# MPU-Peripherals.net
KiCad netlist of a schematic drawn in Altium Designer
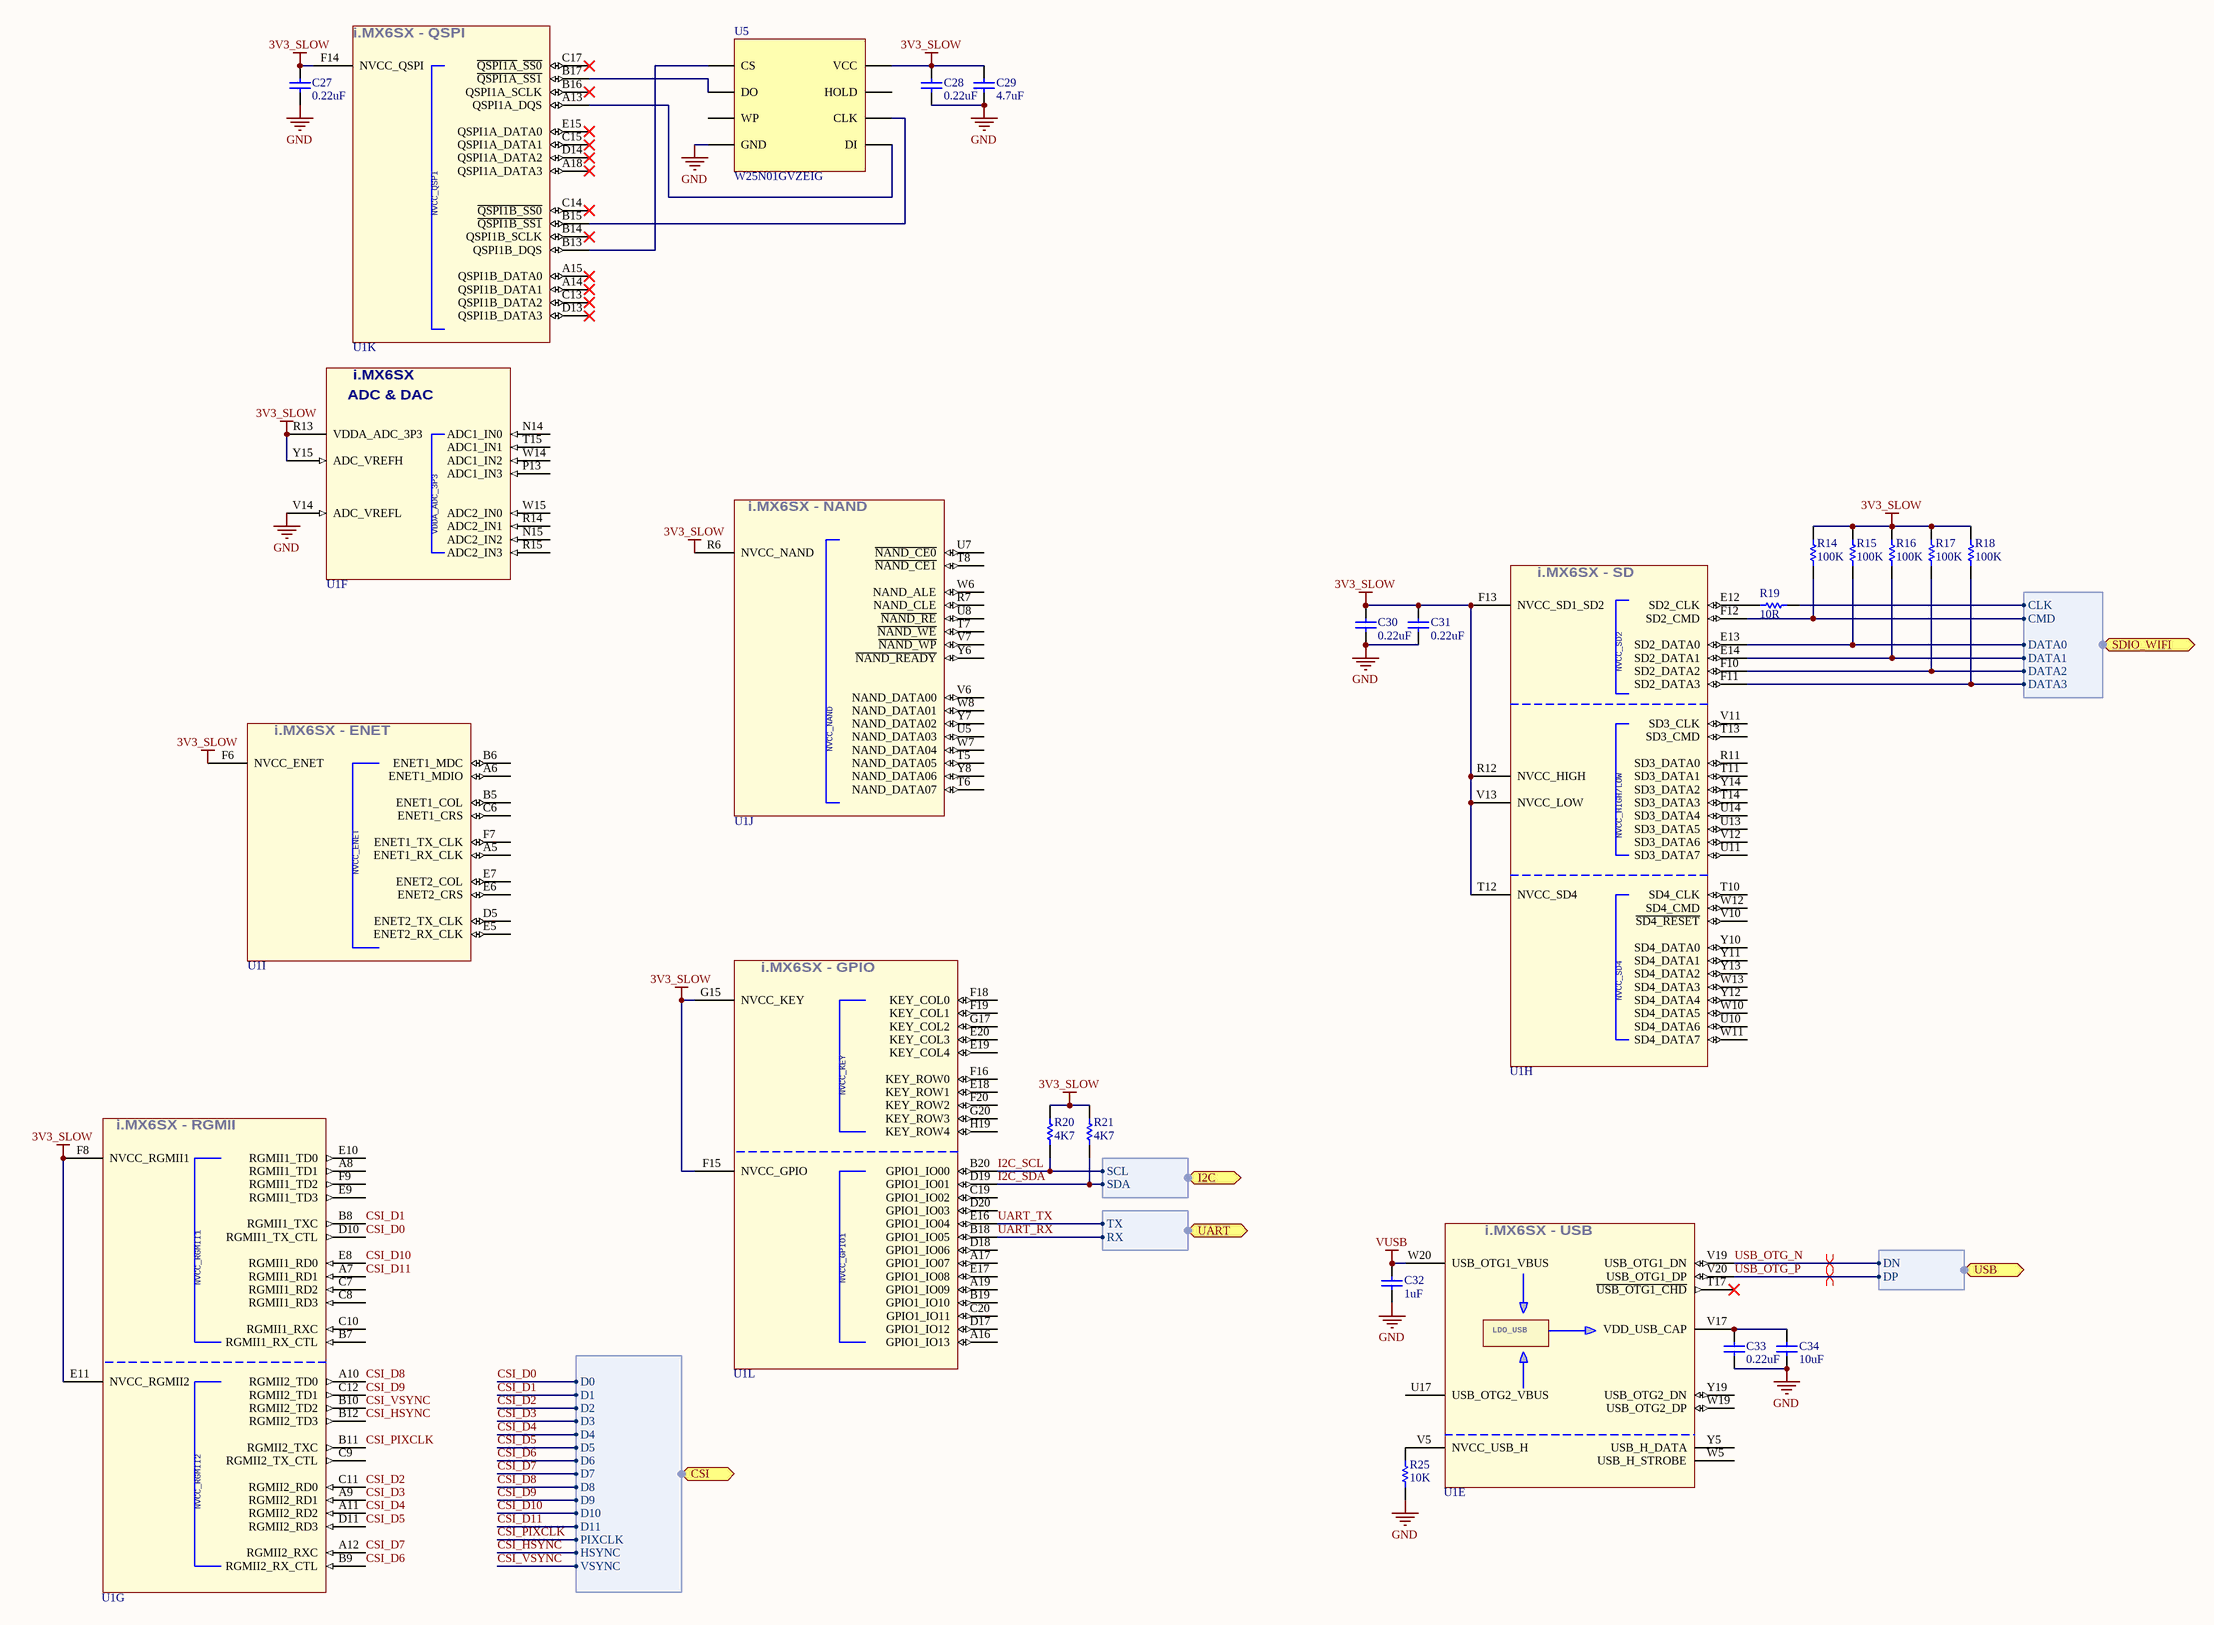
[diagram p0: MPU-Peripherals.SchDoc]

(export (version "E")
  (design (tool "Eeschema 10.0.6"))
  (components
    (comp (ref "C27")
      (value "0.22uF")
      (footprint "C0402[1005X55]")
      (description "0.22uF 6.3V 10% 0402 (1005 Metric)")
      (fields (field (name "PARTNUMBER") "JMK105BJ224KV-F") (field (name "MANUFACTURER") "Taiyo Yuden"))
      (libsource (lib "Capacitors") (part "CAP_0.22uF_6.3V_0402_10%"))
    )
    (comp (ref "C28")
      (value "0.22uF")
      (footprint "C0402[1005X55]")
      (description "0.22uF 6.3V 10% 0402 (1005 Metric)")
      (fields (field (name "PARTNUMBER") "JMK105BJ224KV-F") (field (name "MANUFACTURER") "Taiyo Yuden"))
      (libsource (lib "Capacitors") (part "CAP_0.22uF_6.3V_0402_10%"))
    )
    (comp (ref "C29")
      (value "4.7uF")
      (footprint "C0402[1005X55]")
      (description "4.7uF 6.3V 20% 0402 (1005 Metric)")
      (fields (field (name "PARTNUMBER") "GRM155R60J475ME47D") (field (name "MANUFACTURER") "Murata"))
      (libsource (lib "Capacitors") (part "CAP_4.7uF_6.3V_0402_20%"))
    )
    (comp (ref "C30")
      (value "0.22uF")
      (footprint "C0402[1005X55]")
      (description "0.22uF 6.3V 10% 0402 (1005 Metric)")
      (fields (field (name "PARTNUMBER") "JMK105BJ224KV-F") (field (name "MANUFACTURER") "Taiyo Yuden"))
      (libsource (lib "Capacitors") (part "CAP_0.22uF_6.3V_0402_10%"))
    )
    (comp (ref "C31")
      (value "0.22uF")
      (footprint "C0402[1005X55]")
      (description "0.22uF 6.3V 10% 0402 (1005 Metric)")
      (fields (field (name "PARTNUMBER") "JMK105BJ224KV-F") (field (name "MANUFACTURER") "Taiyo Yuden"))
      (libsource (lib "Capacitors") (part "CAP_0.22uF_6.3V_0402_10%"))
    )
    (comp (ref "C32")
      (value "1uF")
      (footprint "C0402[1005X55]")
      (description "1uF 16V 10% 0402 (1005 Metric)")
      (fields (field (name "PARTNUMBER") "GRM155R61C105KE01D") (field (name "MANUFACTURER") "Murata"))
      (libsource (lib "Capacitors") (part "CAP_1uF_16V_0402_10%"))
    )
    (comp (ref "C33")
      (value "0.22uF")
      (footprint "C0402[1005X55]")
      (description "0.22uF 6.3V 10% 0402 (1005 Metric)")
      (fields (field (name "PARTNUMBER") "JMK105BJ224KV-F") (field (name "MANUFACTURER") "Taiyo Yuden"))
      (libsource (lib "Capacitors") (part "CAP_0.22uF_6.3V_0402_10%"))
    )
    (comp (ref "C34")
      (value "10uF")
      (footprint "C0402[1005X55]")
      (description "10uF 6.3V 20% 0402 (1005 Metric)")
      (fields (field (name "PARTNUMBER") "GRM155R60J106ME44D") (field (name "MANUFACTURER") "Murata"))
      (libsource (lib "Capacitors") (part "CAP_10uF_6.3V_0402_20%"))
    )
    (comp (ref "R14")
      (value "100K")
      (footprint "R0402[1005]")
      (description "100K 0.063W 1% 0402 (1005 Metric)")
      (fields (field (name "MANUFACTURER") "KOA Speer") (field (name "PARTNUMBER") "RK73H1ETTP1003F"))
      (libsource (lib "Resistors") (part "RES_100K_0402_1%"))
    )
    (comp (ref "R15")
      (value "100K")
      (footprint "R0402[1005]")
      (description "100K 0.063W 1% 0402 (1005 Metric)")
      (fields (field (name "MANUFACTURER") "KOA Speer") (field (name "PARTNUMBER") "RK73H1ETTP1003F"))
      (libsource (lib "Resistors") (part "RES_100K_0402_1%"))
    )
    (comp (ref "R16")
      (value "100K")
      (footprint "R0402[1005]")
      (description "100K 0.063W 1% 0402 (1005 Metric)")
      (fields (field (name "MANUFACTURER") "KOA Speer") (field (name "PARTNUMBER") "RK73H1ETTP1003F"))
      (libsource (lib "Resistors") (part "RES_100K_0402_1%"))
    )
    (comp (ref "R17")
      (value "100K")
      (footprint "R0402[1005]")
      (description "100K 0.063W 1% 0402 (1005 Metric)")
      (fields (field (name "MANUFACTURER") "KOA Speer") (field (name "PARTNUMBER") "RK73H1ETTP1003F"))
      (libsource (lib "Resistors") (part "RES_100K_0402_1%"))
    )
    (comp (ref "R18")
      (value "100K")
      (footprint "R0402[1005]")
      (description "100K 0.063W 1% 0402 (1005 Metric)")
      (fields (field (name "MANUFACTURER") "KOA Speer") (field (name "PARTNUMBER") "RK73H1ETTP1003F"))
      (libsource (lib "Resistors") (part "RES_100K_0402_1%"))
    )
    (comp (ref "R19")
      (value "10R")
      (footprint "R0402[1005]")
      (description "10R 0.063W 1% 0402 (1005 Metric)")
      (fields (field (name "MANUFACTURER") "KOA Speer") (field (name "PARTNUMBER") "RK73H1ETTP10R0F"))
      (libsource (lib "Resistors") (part "RES_10R_0402_1%"))
    )
    (comp (ref "R20")
      (value "4K7")
      (footprint "R0402[1005]")
      (description "4K7 0.063W 1% 0402 (1005 Metric)")
      (fields (field (name "MANUFACTURER") "KOA Speer") (field (name "PARTNUMBER") "RK73H1ETTP4701F"))
      (libsource (lib "Resistors") (part "RES_4K7_0402_1%"))
    )
    (comp (ref "R21")
      (value "4K7")
      (footprint "R0402[1005]")
      (description "4K7 0.063W 1% 0402 (1005 Metric)")
      (fields (field (name "MANUFACTURER") "KOA Speer") (field (name "PARTNUMBER") "RK73H1ETTP4701F"))
      (libsource (lib "Resistors") (part "RES_4K7_0402_1%"))
    )
    (comp (ref "R25")
      (value "10K")
      (footprint "R0402[1005]")
      (description "10K 0.063W 1% 0402 (1005 Metric)")
      (fields (field (name "MANUFACTURER") "KOA Speer") (field (name "PARTNUMBER") "RK73H1ETTP1002F"))
      (libsource (lib "Resistors") (part "RES_10K_0402_1%"))
    )
    (comp (ref "U1")
      (value "MCIMX6X3EVO10AB")
      (footprint "BGA-400")
      (description "IC MPU I.MX6SX 1GHZ 400MAPBGA")
      (fields (field (name "MANUFACTURER") "NXP"))
      (libsource (lib "ICs") (part "MCIMX6X3EVO10AB"))
    )
    (comp (ref "U5")
      (value "W25N01GVZEIG")
      (footprint "WSON-8 (6X8MM)")
      (fields (field (name "MANUFACTURER") "Winbond Electronics"))
      (libsource (lib "ICs") (part "W25N01GVZEIG"))
    )
  )
  (nets
    (net (code "6") (name "/CLK") (class "Default")
      (node (ref "R19") (pin "2") (pinfunction "2_2") (pintype "passive"))
    )
    (net (code "7") (name "/CMD") (class "Default")
      (node (ref "R14") (pin "1") (pinfunction "1_1") (pintype "passive"))
      (node (ref "U1") (pin "F12") (pinfunction "SD2_CMD_F12") (pintype "bidirectional"))
    )
    (net (code "8") (name "/CSI_D0") (class "Default")
      (node (ref "U1") (pin "D10") (pinfunction "RGMII1_TX_CTL_D10") (pintype "output"))
    )
    (net (code "9") (name "/CSI_D1") (class "Default")
      (node (ref "U1") (pin "B8") (pinfunction "RGMII1_TXC_B8") (pintype "output"))
    )
    (net (code "10") (name "/CSI_D2") (class "Default")
      (node (ref "U1") (pin "C11") (pinfunction "RGMII2_RD0_C11") (pintype "input"))
    )
    (net (code "11") (name "/CSI_D3") (class "Default")
      (node (ref "U1") (pin "A9") (pinfunction "RGMII2_RD1_A9") (pintype "input"))
    )
    (net (code "12") (name "/CSI_D4") (class "Default")
      (node (ref "U1") (pin "A11") (pinfunction "RGMII2_RD2_A11") (pintype "input"))
    )
    (net (code "13") (name "/CSI_D5") (class "Default")
      (node (ref "U1") (pin "D11") (pinfunction "RGMII2_RD3_D11") (pintype "input"))
    )
    (net (code "14") (name "/CSI_D6") (class "Default")
      (node (ref "U1") (pin "B9") (pinfunction "RGMII2_RX_CTL_B9") (pintype "input"))
    )
    (net (code "15") (name "/CSI_D7") (class "Default")
      (node (ref "U1") (pin "A12") (pinfunction "RGMII2_RXC_A12") (pintype "input"))
    )
    (net (code "16") (name "/CSI_D8") (class "Default")
      (node (ref "U1") (pin "A10") (pinfunction "RGMII2_TD0_A10") (pintype "output"))
    )
    (net (code "17") (name "/CSI_D9") (class "Default")
      (node (ref "U1") (pin "C12") (pinfunction "RGMII2_TD1_C12") (pintype "output"))
    )
    (net (code "18") (name "/CSI_D10") (class "Default")
      (node (ref "U1") (pin "E8") (pinfunction "RGMII1_RD0_E8") (pintype "input"))
    )
    (net (code "19") (name "/CSI_D11") (class "Default")
      (node (ref "U1") (pin "A7") (pinfunction "RGMII1_RD1_A7") (pintype "input"))
    )
    (net (code "20") (name "/CSI_HSYNC") (class "Default")
      (node (ref "U1") (pin "B12") (pinfunction "RGMII2_TD3_B12") (pintype "output"))
    )
    (net (code "21") (name "/CSI_PIXCLK") (class "Default")
      (node (ref "U1") (pin "B11") (pinfunction "RGMII2_TXC_B11") (pintype "output"))
    )
    (net (code "22") (name "/CSI_VSYNC") (class "Default")
      (node (ref "U1") (pin "B10") (pinfunction "RGMII2_TD2_B10") (pintype "output"))
    )
    (net (code "23") (name "/DATA0") (class "Default")
      (node (ref "R15") (pin "1") (pinfunction "1_1") (pintype "passive"))
      (node (ref "U1") (pin "E13") (pinfunction "SD2_DATA0_E13") (pintype "bidirectional"))
    )
    (net (code "24") (name "/DATA1") (class "Default")
      (node (ref "R16") (pin "1") (pinfunction "1_1") (pintype "passive"))
      (node (ref "U1") (pin "E14") (pinfunction "SD2_DATA1_E14") (pintype "bidirectional"))
    )
    (net (code "25") (name "/DATA2") (class "Default")
      (node (ref "R17") (pin "1") (pinfunction "1_1") (pintype "passive"))
      (node (ref "U1") (pin "F10") (pinfunction "SD2_DATA2_F10") (pintype "bidirectional"))
    )
    (net (code "26") (name "/DATA3") (class "Default")
      (node (ref "R18") (pin "1") (pinfunction "1_1") (pintype "passive"))
      (node (ref "U1") (pin "F11") (pinfunction "SD2_DATA3_F11") (pintype "bidirectional"))
    )
    (net (code "27") (name "/I2C_SCL") (class "Default")
      (node (ref "R20") (pin "1") (pinfunction "1_1") (pintype "passive"))
      (node (ref "U1") (pin "B20") (pinfunction "GPIO1_IO00_B20") (pintype "bidirectional"))
    )
    (net (code "28") (name "/I2C_SDA") (class "Default")
      (node (ref "R21") (pin "1") (pinfunction "1_1") (pintype "passive"))
      (node (ref "U1") (pin "D19") (pinfunction "GPIO1_IO01_D19") (pintype "bidirectional"))
    )
    (net (code "29") (name "/UART_RX") (class "Default")
      (node (ref "U1") (pin "B18") (pinfunction "GPIO1_IO05_B18") (pintype "bidirectional"))
    )
    (net (code "30") (name "/UART_TX") (class "Default")
      (node (ref "U1") (pin "E16") (pinfunction "GPIO1_IO04_E16") (pintype "bidirectional"))
    )
    (net (code "31") (name "/USB_OTG_N") (class "Default")
      (node (ref "U1") (pin "V19") (pinfunction "USB_OTG1_DN_V19") (pintype "bidirectional"))
    )
    (net (code "32") (name "/USB_OTG_P") (class "Default")
      (node (ref "U1") (pin "V20") (pinfunction "USB_OTG1_DP_V20") (pintype "bidirectional"))
    )
    (net (code "38") (name "3V3_SLOW") (class "Default")
      (node (ref "C27") (pin "2") (pinfunction "2_2") (pintype "passive"))
      (node (ref "C28") (pin "2") (pinfunction "2_2") (pintype "passive"))
      (node (ref "C29") (pin "2") (pinfunction "2_2") (pintype "passive"))
      (node (ref "C30") (pin "2") (pinfunction "2_2") (pintype "passive"))
      (node (ref "C31") (pin "2") (pinfunction "2_2") (pintype "passive"))
      (node (ref "R14") (pin "2") (pinfunction "2_2") (pintype "passive"))
      (node (ref "R15") (pin "2") (pinfunction "2_2") (pintype "passive"))
      (node (ref "R16") (pin "2") (pinfunction "2_2") (pintype "passive"))
      (node (ref "R17") (pin "2") (pinfunction "2_2") (pintype "passive"))
      (node (ref "R18") (pin "2") (pinfunction "2_2") (pintype "passive"))
      (node (ref "R20") (pin "2") (pinfunction "2_2") (pintype "passive"))
      (node (ref "R21") (pin "2") (pinfunction "2_2") (pintype "passive"))
      (node (ref "U1") (pin "E11") (pinfunction "NVCC_RGMII2_E11") (pintype "power_in"))
      (node (ref "U1") (pin "F13") (pinfunction "NVCC_SD1_SD2_F13") (pintype "power_in"))
      (node (ref "U1") (pin "F14") (pinfunction "NVCC_QSPI_F14") (pintype "power_in"))
      (node (ref "U1") (pin "F15") (pinfunction "NVCC_GPIO_F15") (pintype "power_in"))
      (node (ref "U1") (pin "F6") (pinfunction "NVCC_ENET_F6") (pintype "power_in"))
      (node (ref "U1") (pin "F8") (pinfunction "NVCC_RGMII1_F8") (pintype "power_in"))
      (node (ref "U1") (pin "G15") (pinfunction "NVCC_KEY_G15") (pintype "power_in"))
      (node (ref "U1") (pin "R12") (pinfunction "NVCC_HIGH_R12") (pintype "power_in"))
      (node (ref "U1") (pin "R13") (pinfunction "VDDA_ADC_3P3_R13") (pintype "power_in"))
      (node (ref "U1") (pin "R6") (pinfunction "NVCC_NAND_R6") (pintype "power_in"))
      (node (ref "U1") (pin "T12") (pinfunction "NVCC_SD4_T12") (pintype "power_in"))
      (node (ref "U1") (pin "V13") (pinfunction "NVCC_LOW_V13") (pintype "power_in"))
      (node (ref "U1") (pin "Y15") (pinfunction "ADC_VREFH_Y15") (pintype "input"))
      (node (ref "U5") (pin "8") (pinfunction "VCC_8") (pintype "passive"))
    )
    (net (code "39") (name "GND") (class "Default")
      (node (ref "C27") (pin "1") (pinfunction "1_1") (pintype "passive"))
      (node (ref "C28") (pin "1") (pinfunction "1_1") (pintype "passive"))
      (node (ref "C29") (pin "1") (pinfunction "1_1") (pintype "passive"))
      (node (ref "C30") (pin "1") (pinfunction "1_1") (pintype "passive"))
      (node (ref "C31") (pin "1") (pinfunction "1_1") (pintype "passive"))
      (node (ref "C32") (pin "1") (pinfunction "1_1") (pintype "passive"))
      (node (ref "C33") (pin "1") (pinfunction "1_1") (pintype "passive"))
      (node (ref "C34") (pin "1") (pinfunction "1_1") (pintype "passive"))
      (node (ref "R25") (pin "1") (pinfunction "1_1") (pintype "passive"))
      (node (ref "U1") (pin "V14") (pinfunction "ADC_VREFL_V14") (pintype "input"))
      (node (ref "U5") (pin "4") (pinfunction "GND_4") (pintype "passive"))
    )
    (net (code "40") (name "Net-(U1E-NVCC_USB_H)") (class "Default")
      (node (ref "R25") (pin "2") (pinfunction "2_2") (pintype "passive"))
      (node (ref "U1") (pin "V5") (pinfunction "NVCC_USB_H_V5") (pintype "power_in"))
    )
    (net (code "41") (name "Net-(U1E-VDD_USB_CAP)") (class "Default")
      (node (ref "C33") (pin "2") (pinfunction "2_2") (pintype "passive"))
      (node (ref "C34") (pin "2") (pinfunction "2_2") (pintype "passive"))
      (node (ref "U1") (pin "V17") (pinfunction "VDD_USB_CAP_V17") (pintype "power_in"))
    )
    (net (code "42") (name "Net-(U1H-SD2_CLK)") (class "Default")
      (node (ref "R19") (pin "1") (pinfunction "1_1") (pintype "passive"))
      (node (ref "U1") (pin "E12") (pinfunction "SD2_CLK_E12") (pintype "bidirectional"))
    )
    (net (code "43") (name "Net-(U1K-QSPI1A_DQS)") (class "Default")
      (node (ref "U1") (pin "A13") (pinfunction "QSPI1A_DQS_A13") (pintype "bidirectional"))
      (node (ref "U5") (pin "5") (pinfunction "DI_5") (pintype "power_in"))
    )
    (net (code "44") (name "Net-(U1K-QSPI1B_DQS)") (class "Default")
      (node (ref "U1") (pin "B13") (pinfunction "QSPI1B_DQS_B13") (pintype "bidirectional"))
      (node (ref "U5") (pin "1") (pinfunction "CS_1") (pintype "passive"))
    )
    (net (code "45") (name "Net-(U1K-~{QSPI1A_SS1})") (class "Default")
      (node (ref "U1") (pin "B17") (pinfunction "~{QSPI1A_SS1}_B17") (pintype "bidirectional"))
      (node (ref "U5") (pin "2") (pinfunction "DO_2") (pintype "passive"))
    )
    (net (code "46") (name "Net-(U1K-~{QSPI1B_SS1})") (class "Default")
      (node (ref "U1") (pin "B15") (pinfunction "~{QSPI1B_SS1}_B15") (pintype "bidirectional"))
      (node (ref "U5") (pin "6") (pinfunction "CLK_6") (pintype "passive"))
    )
    (net (code "47") (name "VUSB") (class "Default")
      (node (ref "C32") (pin "2") (pinfunction "2_2") (pintype "passive"))
      (node (ref "U1") (pin "W20") (pinfunction "USB_OTG1_VBUS_W20") (pintype "power_in"))
    )
    (net (code "48") (name "unconnected-(U1E-USB_H_DATA-PadY5)") (class "Default")
      (node (ref "U1") (pin "Y5") (pinfunction "USB_H_DATA_Y5") (pintype "passive"))
    )
    (net (code "49") (name "unconnected-(U1E-USB_H_STROBE-PadW5)") (class "Default")
      (node (ref "U1") (pin "W5") (pinfunction "USB_H_STROBE_W5") (pintype "passive"))
    )
    (net (code "50") (name "unconnected-(U1E-USB_OTG2_DN-PadY19)") (class "Default")
      (node (ref "U1") (pin "Y19") (pinfunction "USB_OTG2_DN_Y19") (pintype "bidirectional"))
    )
    (net (code "51") (name "unconnected-(U1E-USB_OTG2_DP-PadW19)") (class "Default")
      (node (ref "U1") (pin "W19") (pinfunction "USB_OTG2_DP_W19") (pintype "bidirectional"))
    )
    (net (code "52") (name "unconnected-(U1E-USB_OTG2_VBUS-PadU17)") (class "Default")
      (node (ref "U1") (pin "U17") (pinfunction "USB_OTG2_VBUS_U17") (pintype "power_in"))
    )
    (net (code "53") (name "unconnected-(U1E-~{USB_OTG1_CHD}-PadT17)") (class "Default")
      (node (ref "U1") (pin "T17") (pinfunction "~{USB_OTG1_CHD}_T17") (pintype "output+no_connect"))
    )
    (net (code "54") (name "unconnected-(U1F-ADC1_IN0-PadN14)") (class "Default")
      (node (ref "U1") (pin "N14") (pinfunction "ADC1_IN0_N14") (pintype "input"))
    )
    (net (code "55") (name "unconnected-(U1F-ADC1_IN1-PadT15)") (class "Default")
      (node (ref "U1") (pin "T15") (pinfunction "ADC1_IN1_T15") (pintype "input"))
    )
    (net (code "56") (name "unconnected-(U1F-ADC1_IN2-PadW14)") (class "Default")
      (node (ref "U1") (pin "W14") (pinfunction "ADC1_IN2_W14") (pintype "input"))
    )
    (net (code "57") (name "unconnected-(U1F-ADC1_IN3-PadP13)") (class "Default")
      (node (ref "U1") (pin "P13") (pinfunction "ADC1_IN3_P13") (pintype "input"))
    )
    (net (code "58") (name "unconnected-(U1F-ADC2_IN0-PadW15)") (class "Default")
      (node (ref "U1") (pin "W15") (pinfunction "ADC2_IN0_W15") (pintype "input"))
    )
    (net (code "59") (name "unconnected-(U1F-ADC2_IN1-PadR14)") (class "Default")
      (node (ref "U1") (pin "R14") (pinfunction "ADC2_IN1_R14") (pintype "input"))
    )
    (net (code "60") (name "unconnected-(U1F-ADC2_IN2-PadN15)") (class "Default")
      (node (ref "U1") (pin "N15") (pinfunction "ADC2_IN2_N15") (pintype "input"))
    )
    (net (code "61") (name "unconnected-(U1F-ADC2_IN3-PadR15)") (class "Default")
      (node (ref "U1") (pin "R15") (pinfunction "ADC2_IN3_R15") (pintype "input"))
    )
    (net (code "62") (name "unconnected-(U1G-RGMII1_RD2-PadC7)") (class "Default")
      (node (ref "U1") (pin "C7") (pinfunction "RGMII1_RD2_C7") (pintype "input"))
    )
    (net (code "63") (name "unconnected-(U1G-RGMII1_RD3-PadC8)") (class "Default")
      (node (ref "U1") (pin "C8") (pinfunction "RGMII1_RD3_C8") (pintype "input"))
    )
    (net (code "64") (name "unconnected-(U1G-RGMII1_RXC-PadC10)") (class "Default")
      (node (ref "U1") (pin "C10") (pinfunction "RGMII1_RXC_C10") (pintype "input"))
    )
    (net (code "65") (name "unconnected-(U1G-RGMII1_RX_CTL-PadB7)") (class "Default")
      (node (ref "U1") (pin "B7") (pinfunction "RGMII1_RX_CTL_B7") (pintype "input"))
    )
    (net (code "66") (name "unconnected-(U1G-RGMII1_TD0-PadE10)") (class "Default")
      (node (ref "U1") (pin "E10") (pinfunction "RGMII1_TD0_E10") (pintype "output"))
    )
    (net (code "67") (name "unconnected-(U1G-RGMII1_TD1-PadA8)") (class "Default")
      (node (ref "U1") (pin "A8") (pinfunction "RGMII1_TD1_A8") (pintype "output"))
    )
    (net (code "68") (name "unconnected-(U1G-RGMII1_TD2-PadF9)") (class "Default")
      (node (ref "U1") (pin "F9") (pinfunction "RGMII1_TD2_F9") (pintype "output"))
    )
    (net (code "69") (name "unconnected-(U1G-RGMII1_TD3-PadE9)") (class "Default")
      (node (ref "U1") (pin "E9") (pinfunction "RGMII1_TD3_E9") (pintype "output"))
    )
    (net (code "70") (name "unconnected-(U1G-RGMII2_TX_CTL-PadC9)") (class "Default")
      (node (ref "U1") (pin "C9") (pinfunction "RGMII2_TX_CTL_C9") (pintype "output"))
    )
    (net (code "71") (name "unconnected-(U1H-SD3_CLK-PadV11)") (class "Default")
      (node (ref "U1") (pin "V11") (pinfunction "SD3_CLK_V11") (pintype "bidirectional"))
    )
    (net (code "72") (name "unconnected-(U1H-SD3_CMD-PadT13)") (class "Default")
      (node (ref "U1") (pin "T13") (pinfunction "SD3_CMD_T13") (pintype "bidirectional"))
    )
    (net (code "73") (name "unconnected-(U1H-SD3_DATA0-PadR11)") (class "Default")
      (node (ref "U1") (pin "R11") (pinfunction "SD3_DATA0_R11") (pintype "bidirectional"))
    )
    (net (code "74") (name "unconnected-(U1H-SD3_DATA1-PadT11)") (class "Default")
      (node (ref "U1") (pin "T11") (pinfunction "SD3_DATA1_T11") (pintype "bidirectional"))
    )
    (net (code "75") (name "unconnected-(U1H-SD3_DATA2-PadY14)") (class "Default")
      (node (ref "U1") (pin "Y14") (pinfunction "SD3_DATA2_Y14") (pintype "bidirectional"))
    )
    (net (code "76") (name "unconnected-(U1H-SD3_DATA3-PadT14)") (class "Default")
      (node (ref "U1") (pin "T14") (pinfunction "SD3_DATA3_T14") (pintype "bidirectional"))
    )
    (net (code "77") (name "unconnected-(U1H-SD3_DATA4-PadU14)") (class "Default")
      (node (ref "U1") (pin "U14") (pinfunction "SD3_DATA4_U14") (pintype "bidirectional"))
    )
    (net (code "78") (name "unconnected-(U1H-SD3_DATA5-PadU13)") (class "Default")
      (node (ref "U1") (pin "U13") (pinfunction "SD3_DATA5_U13") (pintype "bidirectional"))
    )
    (net (code "79") (name "unconnected-(U1H-SD3_DATA6-PadV12)") (class "Default")
      (node (ref "U1") (pin "V12") (pinfunction "SD3_DATA6_V12") (pintype "bidirectional"))
    )
    (net (code "80") (name "unconnected-(U1H-SD3_DATA7-PadU11)") (class "Default")
      (node (ref "U1") (pin "U11") (pinfunction "SD3_DATA7_U11") (pintype "bidirectional"))
    )
    (net (code "81") (name "unconnected-(U1H-SD4_CLK-PadT10)") (class "Default")
      (node (ref "U1") (pin "T10") (pinfunction "SD4_CLK_T10") (pintype "bidirectional"))
    )
    (net (code "82") (name "unconnected-(U1H-SD4_CMD-PadW12)") (class "Default")
      (node (ref "U1") (pin "W12") (pinfunction "SD4_CMD_W12") (pintype "bidirectional"))
    )
    (net (code "83") (name "unconnected-(U1H-SD4_DATA0-PadY10)") (class "Default")
      (node (ref "U1") (pin "Y10") (pinfunction "SD4_DATA0_Y10") (pintype "bidirectional"))
    )
    (net (code "84") (name "unconnected-(U1H-SD4_DATA1-PadY11)") (class "Default")
      (node (ref "U1") (pin "Y11") (pinfunction "SD4_DATA1_Y11") (pintype "bidirectional"))
    )
    (net (code "85") (name "unconnected-(U1H-SD4_DATA2-PadY13)") (class "Default")
      (node (ref "U1") (pin "Y13") (pinfunction "SD4_DATA2_Y13") (pintype "bidirectional"))
    )
    (net (code "86") (name "unconnected-(U1H-SD4_DATA3-PadW13)") (class "Default")
      (node (ref "U1") (pin "W13") (pinfunction "SD4_DATA3_W13") (pintype "bidirectional"))
    )
    (net (code "87") (name "unconnected-(U1H-SD4_DATA4-PadY12)") (class "Default")
      (node (ref "U1") (pin "Y12") (pinfunction "SD4_DATA4_Y12") (pintype "bidirectional"))
    )
    (net (code "88") (name "unconnected-(U1H-SD4_DATA5-PadW10)") (class "Default")
      (node (ref "U1") (pin "W10") (pinfunction "SD4_DATA5_W10") (pintype "bidirectional"))
    )
    (net (code "89") (name "unconnected-(U1H-SD4_DATA6-PadU10)") (class "Default")
      (node (ref "U1") (pin "U10") (pinfunction "SD4_DATA6_U10") (pintype "bidirectional"))
    )
    (net (code "90") (name "unconnected-(U1H-SD4_DATA7-PadW11)") (class "Default")
      (node (ref "U1") (pin "W11") (pinfunction "SD4_DATA7_W11") (pintype "bidirectional"))
    )
    (net (code "91") (name "unconnected-(U1H-~{SD4_RESET}-PadV10)") (class "Default")
      (node (ref "U1") (pin "V10") (pinfunction "~{SD4_RESET}_V10") (pintype "bidirectional"))
    )
    (net (code "92") (name "unconnected-(U1I-ENET1_COL-PadB5)") (class "Default")
      (node (ref "U1") (pin "B5") (pinfunction "ENET1_COL_B5") (pintype "bidirectional"))
    )
    (net (code "93") (name "unconnected-(U1I-ENET1_CRS-PadC6)") (class "Default")
      (node (ref "U1") (pin "C6") (pinfunction "ENET1_CRS_C6") (pintype "bidirectional"))
    )
    (net (code "94") (name "unconnected-(U1I-ENET1_MDC-PadB6)") (class "Default")
      (node (ref "U1") (pin "B6") (pinfunction "ENET1_MDC_B6") (pintype "bidirectional"))
    )
    (net (code "95") (name "unconnected-(U1I-ENET1_MDIO-PadA6)") (class "Default")
      (node (ref "U1") (pin "A6") (pinfunction "ENET1_MDIO_A6") (pintype "bidirectional"))
    )
    (net (code "96") (name "unconnected-(U1I-ENET1_RX_CLK-PadA5)") (class "Default")
      (node (ref "U1") (pin "A5") (pinfunction "ENET1_RX_CLK_A5") (pintype "bidirectional"))
    )
    (net (code "97") (name "unconnected-(U1I-ENET1_TX_CLK-PadF7)") (class "Default")
      (node (ref "U1") (pin "F7") (pinfunction "ENET1_TX_CLK_F7") (pintype "bidirectional"))
    )
    (net (code "98") (name "unconnected-(U1I-ENET2_COL-PadE7)") (class "Default")
      (node (ref "U1") (pin "E7") (pinfunction "ENET2_COL_E7") (pintype "bidirectional"))
    )
    (net (code "99") (name "unconnected-(U1I-ENET2_CRS-PadE6)") (class "Default")
      (node (ref "U1") (pin "E6") (pinfunction "ENET2_CRS_E6") (pintype "bidirectional"))
    )
    (net (code "100") (name "unconnected-(U1I-ENET2_RX_CLK-PadE5)") (class "Default")
      (node (ref "U1") (pin "E5") (pinfunction "ENET2_RX_CLK_E5") (pintype "bidirectional"))
    )
    (net (code "101") (name "unconnected-(U1I-ENET2_TX_CLK-PadD5)") (class "Default")
      (node (ref "U1") (pin "D5") (pinfunction "ENET2_TX_CLK_D5") (pintype "bidirectional"))
    )
    (net (code "102") (name "unconnected-(U1J-NAND_ALE-PadW6)") (class "Default")
      (node (ref "U1") (pin "W6") (pinfunction "NAND_ALE_W6") (pintype "bidirectional"))
    )
    (net (code "103") (name "unconnected-(U1J-NAND_CLE-PadR7)") (class "Default")
      (node (ref "U1") (pin "R7") (pinfunction "NAND_CLE_R7") (pintype "bidirectional"))
    )
    (net (code "104") (name "unconnected-(U1J-NAND_DATA00-PadV6)") (class "Default")
      (node (ref "U1") (pin "V6") (pinfunction "NAND_DATA00_V6") (pintype "bidirectional"))
    )
    (net (code "105") (name "unconnected-(U1J-NAND_DATA01-PadW8)") (class "Default")
      (node (ref "U1") (pin "W8") (pinfunction "NAND_DATA01_W8") (pintype "bidirectional"))
    )
    (net (code "106") (name "unconnected-(U1J-NAND_DATA02-PadY7)") (class "Default")
      (node (ref "U1") (pin "Y7") (pinfunction "NAND_DATA02_Y7") (pintype "bidirectional"))
    )
    (net (code "107") (name "unconnected-(U1J-NAND_DATA03-PadU5)") (class "Default")
      (node (ref "U1") (pin "U5") (pinfunction "NAND_DATA03_U5") (pintype "bidirectional"))
    )
    (net (code "108") (name "unconnected-(U1J-NAND_DATA04-PadW7)") (class "Default")
      (node (ref "U1") (pin "W7") (pinfunction "NAND_DATA04_W7") (pintype "bidirectional"))
    )
    (net (code "109") (name "unconnected-(U1J-NAND_DATA05-PadT5)") (class "Default")
      (node (ref "U1") (pin "T5") (pinfunction "NAND_DATA05_T5") (pintype "bidirectional"))
    )
    (net (code "110") (name "unconnected-(U1J-NAND_DATA06-PadY8)") (class "Default")
      (node (ref "U1") (pin "Y8") (pinfunction "NAND_DATA06_Y8") (pintype "bidirectional"))
    )
    (net (code "111") (name "unconnected-(U1J-NAND_DATA07-PadT6)") (class "Default")
      (node (ref "U1") (pin "T6") (pinfunction "NAND_DATA07_T6") (pintype "bidirectional"))
    )
    (net (code "112") (name "unconnected-(U1J-~{NAND_CE0}-PadU7)") (class "Default")
      (node (ref "U1") (pin "U7") (pinfunction "~{NAND_CE0}_U7") (pintype "bidirectional"))
    )
    (net (code "113") (name "unconnected-(U1J-~{NAND_CE1}-PadT8)") (class "Default")
      (node (ref "U1") (pin "T8") (pinfunction "~{NAND_CE1}_T8") (pintype "bidirectional"))
    )
    (net (code "114") (name "unconnected-(U1J-~{NAND_READY}-PadY6)") (class "Default")
      (node (ref "U1") (pin "Y6") (pinfunction "~{NAND_READY}_Y6") (pintype "bidirectional"))
    )
    (net (code "115") (name "unconnected-(U1J-~{NAND_RE}-PadU8)") (class "Default")
      (node (ref "U1") (pin "U8") (pinfunction "~{NAND_RE}_U8") (pintype "bidirectional"))
    )
    (net (code "116") (name "unconnected-(U1J-~{NAND_WE}-PadT7)") (class "Default")
      (node (ref "U1") (pin "T7") (pinfunction "~{NAND_WE}_T7") (pintype "bidirectional"))
    )
    (net (code "117") (name "unconnected-(U1J-~{NAND_WP}-PadV7)") (class "Default")
      (node (ref "U1") (pin "V7") (pinfunction "~{NAND_WP}_V7") (pintype "bidirectional"))
    )
    (net (code "118") (name "unconnected-(U1K-QSPI1A_DATA0-PadE15)") (class "Default")
      (node (ref "U1") (pin "E15") (pinfunction "QSPI1A_DATA0_E15") (pintype "bidirectional+no_connect"))
    )
    (net (code "119") (name "unconnected-(U1K-QSPI1A_DATA1-PadC15)") (class "Default")
      (node (ref "U1") (pin "C15") (pinfunction "QSPI1A_DATA1_C15") (pintype "bidirectional+no_connect"))
    )
    (net (code "120") (name "unconnected-(U1K-QSPI1A_DATA2-PadD14)") (class "Default")
      (node (ref "U1") (pin "D14") (pinfunction "QSPI1A_DATA2_D14") (pintype "bidirectional+no_connect"))
    )
    (net (code "121") (name "unconnected-(U1K-QSPI1A_DATA3-PadA18)") (class "Default")
      (node (ref "U1") (pin "A18") (pinfunction "QSPI1A_DATA3_A18") (pintype "bidirectional+no_connect"))
    )
    (net (code "122") (name "unconnected-(U1K-QSPI1A_SCLK-PadB16)") (class "Default")
      (node (ref "U1") (pin "B16") (pinfunction "QSPI1A_SCLK_B16") (pintype "bidirectional+no_connect"))
    )
    (net (code "123") (name "unconnected-(U1K-QSPI1B_DATA0-PadA15)") (class "Default")
      (node (ref "U1") (pin "A15") (pinfunction "QSPI1B_DATA0_A15") (pintype "bidirectional+no_connect"))
    )
    (net (code "124") (name "unconnected-(U1K-QSPI1B_DATA1-PadA14)") (class "Default")
      (node (ref "U1") (pin "A14") (pinfunction "QSPI1B_DATA1_A14") (pintype "bidirectional+no_connect"))
    )
    (net (code "125") (name "unconnected-(U1K-QSPI1B_DATA2-PadC13)") (class "Default")
      (node (ref "U1") (pin "C13") (pinfunction "QSPI1B_DATA2_C13") (pintype "bidirectional+no_connect"))
    )
    (net (code "126") (name "unconnected-(U1K-QSPI1B_DATA3-PadD13)") (class "Default")
      (node (ref "U1") (pin "D13") (pinfunction "QSPI1B_DATA3_D13") (pintype "bidirectional+no_connect"))
    )
    (net (code "127") (name "unconnected-(U1K-QSPI1B_SCLK-PadB14)") (class "Default")
      (node (ref "U1") (pin "B14") (pinfunction "QSPI1B_SCLK_B14") (pintype "bidirectional+no_connect"))
    )
    (net (code "128") (name "unconnected-(U1K-~{QSPI1A}_~{SS0}-PadC17)") (class "Default")
      (node (ref "U1") (pin "C17") (pinfunction "~{QSPI1A}_~{SS0}_C17") (pintype "bidirectional+no_connect"))
    )
    (net (code "129") (name "unconnected-(U1K-~{QSPI1B_SS0}-PadC14)") (class "Default")
      (node (ref "U1") (pin "C14") (pinfunction "~{QSPI1B_SS0}_C14") (pintype "bidirectional+no_connect"))
    )
    (net (code "130") (name "unconnected-(U1L-GPIO1_IO02-PadC19)") (class "Default")
      (node (ref "U1") (pin "C19") (pinfunction "GPIO1_IO02_C19") (pintype "bidirectional"))
    )
    (net (code "131") (name "unconnected-(U1L-GPIO1_IO03-PadD20)") (class "Default")
      (node (ref "U1") (pin "D20") (pinfunction "GPIO1_IO03_D20") (pintype "bidirectional"))
    )
    (net (code "132") (name "unconnected-(U1L-GPIO1_IO06-PadD18)") (class "Default")
      (node (ref "U1") (pin "D18") (pinfunction "GPIO1_IO06_D18") (pintype "bidirectional"))
    )
    (net (code "133") (name "unconnected-(U1L-GPIO1_IO07-PadA17)") (class "Default")
      (node (ref "U1") (pin "A17") (pinfunction "GPIO1_IO07_A17") (pintype "bidirectional"))
    )
    (net (code "134") (name "unconnected-(U1L-GPIO1_IO08-PadE17)") (class "Default")
      (node (ref "U1") (pin "E17") (pinfunction "GPIO1_IO08_E17") (pintype "bidirectional"))
    )
    (net (code "135") (name "unconnected-(U1L-GPIO1_IO09-PadA19)") (class "Default")
      (node (ref "U1") (pin "A19") (pinfunction "GPIO1_IO09_A19") (pintype "bidirectional"))
    )
    (net (code "136") (name "unconnected-(U1L-GPIO1_IO10-PadB19)") (class "Default")
      (node (ref "U1") (pin "B19") (pinfunction "GPIO1_IO10_B19") (pintype "bidirectional"))
    )
    (net (code "137") (name "unconnected-(U1L-GPIO1_IO11-PadC20)") (class "Default")
      (node (ref "U1") (pin "C20") (pinfunction "GPIO1_IO11_C20") (pintype "bidirectional"))
    )
    (net (code "138") (name "unconnected-(U1L-GPIO1_IO12-PadD17)") (class "Default")
      (node (ref "U1") (pin "D17") (pinfunction "GPIO1_IO12_D17") (pintype "bidirectional"))
    )
    (net (code "139") (name "unconnected-(U1L-GPIO1_IO13-PadA16)") (class "Default")
      (node (ref "U1") (pin "A16") (pinfunction "GPIO1_IO13_A16") (pintype "bidirectional"))
    )
    (net (code "140") (name "unconnected-(U1L-KEY_COL0-PadF18)") (class "Default")
      (node (ref "U1") (pin "F18") (pinfunction "KEY_COL0_F18") (pintype "bidirectional"))
    )
    (net (code "141") (name "unconnected-(U1L-KEY_COL1-PadF19)") (class "Default")
      (node (ref "U1") (pin "F19") (pinfunction "KEY_COL1_F19") (pintype "bidirectional"))
    )
    (net (code "142") (name "unconnected-(U1L-KEY_COL2-PadG17)") (class "Default")
      (node (ref "U1") (pin "G17") (pinfunction "KEY_COL2_G17") (pintype "bidirectional"))
    )
    (net (code "143") (name "unconnected-(U1L-KEY_COL3-PadE20)") (class "Default")
      (node (ref "U1") (pin "E20") (pinfunction "KEY_COL3_E20") (pintype "bidirectional"))
    )
    (net (code "144") (name "unconnected-(U1L-KEY_COL4-PadE19)") (class "Default")
      (node (ref "U1") (pin "E19") (pinfunction "KEY_COL4_E19") (pintype "bidirectional"))
    )
    (net (code "145") (name "unconnected-(U1L-KEY_ROW0-PadF16)") (class "Default")
      (node (ref "U1") (pin "F16") (pinfunction "KEY_ROW0_F16") (pintype "bidirectional"))
    )
    (net (code "146") (name "unconnected-(U1L-KEY_ROW1-PadE18)") (class "Default")
      (node (ref "U1") (pin "E18") (pinfunction "KEY_ROW1_E18") (pintype "bidirectional"))
    )
    (net (code "147") (name "unconnected-(U1L-KEY_ROW2-PadF20)") (class "Default")
      (node (ref "U1") (pin "F20") (pinfunction "KEY_ROW2_F20") (pintype "bidirectional"))
    )
    (net (code "148") (name "unconnected-(U1L-KEY_ROW3-PadG20)") (class "Default")
      (node (ref "U1") (pin "G20") (pinfunction "KEY_ROW3_G20") (pintype "bidirectional"))
    )
    (net (code "149") (name "unconnected-(U1L-KEY_ROW4-PadH19)") (class "Default")
      (node (ref "U1") (pin "H19") (pinfunction "KEY_ROW4_H19") (pintype "bidirectional"))
    )
    (net (code "150") (name "unconnected-(U5-HOLD-Pad7)") (class "Default")
      (node (ref "U5") (pin "7") (pinfunction "HOLD_7") (pintype "passive"))
    )
    (net (code "151") (name "unconnected-(U5-WP-Pad3)") (class "Default")
      (node (ref "U5") (pin "3") (pinfunction "WP_3") (pintype "passive"))
    )
  )
)
